# BSPD_Test_Board_manufactured_2016-12-12.net
KiCad netlist of a schematic drawn in EAGLE
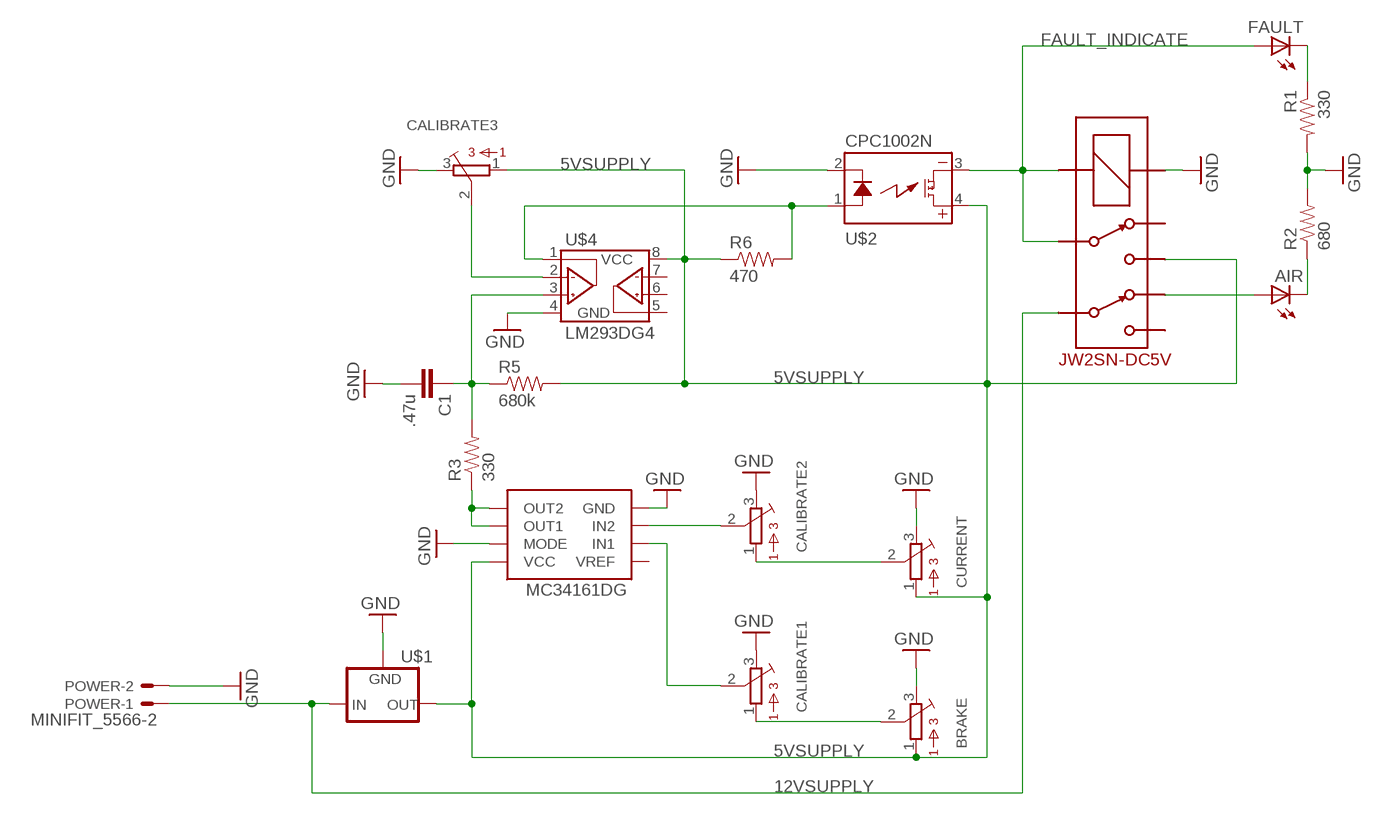
[diagram p0: schematic, sheet 1]

(export (version "E")
  (design (tool "Eeschema 10.0.6"))
  (components
    (comp (ref "AIR")
      (value "LED-5MM")
      (footprint "eagle-import:LED-5MM")
      (libsource (lib "eagle-import") (part "LED-5MM"))
    )
    (comp (ref "BRAKE")
      (value "TRIMPOT_3296C")
      (footprint "eagle-import:TRIMPOT_3296")
      (libsource (lib "eagle-import") (part "TRIMPOT_3296C"))
    )
    (comp (ref "C1")
      (value ".47u")
      (footprint "eagle-import:CAP-PTH-SMALLEZ")
      (libsource (lib "eagle-import") (part "CAPEZ"))
    )
    (comp (ref "CALIBRATE1")
      (value "TRIMPOT_3296C")
      (footprint "eagle-import:TRIMPOT_3296")
      (libsource (lib "eagle-import") (part "TRIMPOT_3296C"))
    )
    (comp (ref "CALIBRATE2")
      (value "TRIMPOT_3296C")
      (footprint "eagle-import:TRIMPOT_3296")
      (libsource (lib "eagle-import") (part "TRIMPOT_3296C"))
    )
    (comp (ref "CALIBRATE3")
      (value "TRIMPOT_3296C")
      (footprint "eagle-import:TRIMPOT_3296")
      (libsource (lib "eagle-import") (part "TRIMPOT_3296C"))
    )
    (comp (ref "CURRENT")
      (value "TRIMPOT_3296C")
      (footprint "eagle-import:TRIMPOT_3296")
      (libsource (lib "eagle-import") (part "TRIMPOT_3296C"))
    )
    (comp (ref "FAULT")
      (value "LED-5MM")
      (footprint "eagle-import:LED-5MM")
      (libsource (lib "eagle-import") (part "LED-5MM"))
    )
    (comp (ref "MC34161DG")
      (value "VOLTAGE_MONITOR_MC34161DG")
      (footprint "eagle-import:SOIC-08")
      (libsource (lib "eagle-import") (part "VOLTAGE_MONITOR_MC34161DG"))
    )
    (comp (ref "POWER")
      (value "MINIFIT_5566-2")
      (footprint "eagle-import:MINIFIT_5566-2")
      (libsource (lib "eagle-import") (part "MINIFIT_5566-2"))
    )
    (comp (ref "R1")
      (value "330")
      (footprint "eagle-import:0805")
      (libsource (lib "eagle-import") (part "RESISTOR0805-RES"))
    )
    (comp (ref "R2")
      (value "680")
      (footprint "eagle-import:0805")
      (libsource (lib "eagle-import") (part "RESISTOR0805-RES"))
    )
    (comp (ref "R3")
      (value "330")
      (footprint "eagle-import:0805")
      (libsource (lib "eagle-import") (part "RESISTOR0805-RES"))
    )
    (comp (ref "R5")
      (value "680k")
      (footprint "eagle-import:AXIAL-0.3EZ")
      (libsource (lib "eagle-import") (part "RESISTOREZ"))
    )
    (comp (ref "R6")
      (value "470")
      (footprint "eagle-import:0805")
      (libsource (lib "eagle-import") (part "RESISTOR0805-RES"))
    )
    (comp (ref "U$1")
      (value "5V_REGULATOR_LM340-NLM340MPX-5.0/NOPB")
      (footprint "eagle-import:SOT223")
      (libsource (lib "eagle-import") (part "5V_REGULATOR_LM340-NLM340MPX-5.0/NOPB"))
    )
    (comp (ref "U$2")
      (value "CPC1002N")
      (footprint "eagle-import:SOP04")
      (libsource (lib "eagle-import") (part "CPC1002N"))
    )
    (comp (ref "U$3")
      (value "DPDT_RELAY_PANASONIC_JW2SN-DC5V")
      (footprint "eagle-import:DPDT_RELAY_PANASONIC_JW2SN")
      (libsource (lib "eagle-import") (part "DPDT_RELAY_PANASONIC_JW2SN-DC5V"))
    )
    (comp (ref "U$4")
      (value "LM293DG4")
      (footprint "eagle-import:SOIC-08")
      (libsource (lib "eagle-import") (part "LM293DG4"))
    )
  )
  (nets
    (net (code "1") (name "/5VSUPPLY") (class "Default")
      (node (ref "BRAKE") (pin "1") (pinfunction "1_1") (pintype "passive"))
      (node (ref "CALIBRATE3") (pin "1") (pinfunction "1_1") (pintype "passive"))
      (node (ref "CURRENT") (pin "1") (pinfunction "1_1") (pintype "passive"))
      (node (ref "MC34161DG") (pin "8") (pinfunction "VCC_8") (pintype "passive"))
      (node (ref "R5") (pin "P$2") (pinfunction "2_P$2") (pintype "passive"))
      (node (ref "R6") (pin "1") (pinfunction "1_1") (pintype "passive"))
      (node (ref "U$1") (pin "3") (pinfunction "OUT_3") (pintype "output"))
      (node (ref "U$2") (pin "4") (pinfunction "DC+_4") (pintype "passive"))
      (node (ref "U$3") (pin "4") (pinfunction "4_4") (pintype "bidirectional"))
      (node (ref "U$4") (pin "8") (pinfunction "VCC_8") (pintype "passive"))
    )
    (net (code "2") (name "/12VSUPPLY") (class "Default")
      (node (ref "POWER") (pin "1") (pinfunction "S_1") (pintype "passive"))
      (node (ref "U$1") (pin "1") (pinfunction "IN_1") (pintype "input"))
      (node (ref "U$3") (pin "6") (pinfunction "6_6") (pintype "bidirectional"))
    )
    (net (code "3") (name "/FAULT_INDICATE") (class "Default")
      (node (ref "FAULT") (pin "A") (pinfunction "A_A") (pintype "passive"))
      (node (ref "U$2") (pin "3") (pinfunction "DC-_3") (pintype "passive"))
      (node (ref "U$3") (pin "3") (pinfunction "3_3") (pintype "bidirectional"))
      (node (ref "U$3") (pin "COIL-") (pinfunction "COIL-_COIL-") (pintype "bidirectional"))
    )
    (net (code "4") (name "GND") (class "Default")
      (node (ref "BRAKE") (pin "3") (pinfunction "3_3") (pintype "passive"))
      (node (ref "C1") (pin "2") (pinfunction "2_2") (pintype "passive"))
      (node (ref "CALIBRATE1") (pin "3") (pinfunction "3_3") (pintype "passive"))
      (node (ref "CALIBRATE2") (pin "3") (pinfunction "3_3") (pintype "passive"))
      (node (ref "CALIBRATE3") (pin "3") (pinfunction "3_3") (pintype "passive"))
      (node (ref "CURRENT") (pin "3") (pinfunction "3_3") (pintype "passive"))
      (node (ref "MC34161DG") (pin "4") (pinfunction "GND_4") (pintype "passive"))
      (node (ref "MC34161DG") (pin "7") (pinfunction "MODE_7") (pintype "passive"))
      (node (ref "POWER") (pin "2") (pinfunction "S_2") (pintype "passive"))
      (node (ref "R1") (pin "2") (pinfunction "2_2") (pintype "passive"))
      (node (ref "R2") (pin "2") (pinfunction "2_2") (pintype "passive"))
      (node (ref "U$1") (pin "2") (pinfunction "GND_2") (pintype "input"))
      (node (ref "U$1") (pin "4") (pinfunction "GND_4") (pintype "input"))
      (node (ref "U$2") (pin "2") (pinfunction "CONTROL-_2") (pintype "passive"))
      (node (ref "U$3") (pin "COIL+") (pinfunction "COIL+_COIL+") (pintype "bidirectional"))
      (node (ref "U$4") (pin "4") (pinfunction "GND_4") (pintype "passive"))
    )
    (net (code "5") (name "Net-(AIR-C)") (class "Default")
      (node (ref "AIR") (pin "K") (pinfunction "C_K") (pintype "passive"))
      (node (ref "R2") (pin "1") (pinfunction "1_1") (pintype "passive"))
    )
    (net (code "6") (name "Net-(AIR-PadA)") (class "Default")
      (node (ref "AIR") (pin "A") (pinfunction "A_A") (pintype "passive"))
      (node (ref "U$3") (pin "7") (pinfunction "7_7") (pintype "bidirectional"))
    )
    (net (code "7") (name "Net-(BRAKE-Pad2)") (class "Default")
      (node (ref "BRAKE") (pin "2") (pinfunction "2_2") (pintype "passive"))
      (node (ref "CALIBRATE1") (pin "1") (pinfunction "1_1") (pintype "passive"))
    )
    (net (code "8") (name "Net-(CALIBRATE2-Pad1)") (class "Default")
      (node (ref "CALIBRATE2") (pin "1") (pinfunction "1_1") (pintype "passive"))
      (node (ref "CURRENT") (pin "2") (pinfunction "2_2") (pintype "passive"))
    )
    (net (code "9") (name "Net-(FAULT-C)") (class "Default")
      (node (ref "FAULT") (pin "K") (pinfunction "C_K") (pintype "passive"))
      (node (ref "R1") (pin "1") (pinfunction "1_1") (pintype "passive"))
    )
    (net (code "10") (name "Net-(MC34161DG-IN1)") (class "Default")
      (node (ref "CALIBRATE1") (pin "2") (pinfunction "2_2") (pintype "passive"))
      (node (ref "MC34161DG") (pin "2") (pinfunction "IN1_2") (pintype "passive"))
    )
    (net (code "11") (name "Net-(MC34161DG-IN2)") (class "Default")
      (node (ref "CALIBRATE2") (pin "2") (pinfunction "2_2") (pintype "passive"))
      (node (ref "MC34161DG") (pin "3") (pinfunction "IN2_3") (pintype "passive"))
    )
    (net (code "12") (name "Net-(MC34161DG-OUT1)") (class "Default")
      (node (ref "MC34161DG") (pin "5") (pinfunction "OUT2_5") (pintype "passive"))
      (node (ref "MC34161DG") (pin "6") (pinfunction "OUT1_6") (pintype "passive"))
      (node (ref "R3") (pin "1") (pinfunction "1_1") (pintype "passive"))
    )
    (net (code "13") (name "Net-(R5-1)") (class "Default")
      (node (ref "C1") (pin "1") (pinfunction "1_1") (pintype "passive"))
      (node (ref "R3") (pin "2") (pinfunction "2_2") (pintype "passive"))
      (node (ref "R5") (pin "P$1") (pinfunction "1_P$1") (pintype "passive"))
      (node (ref "U$4") (pin "3") (pinfunction "1IN+_3") (pintype "passive"))
    )
    (net (code "14") (name "Net-(U$2-CONTROL+)") (class "Default")
      (node (ref "R6") (pin "2") (pinfunction "2_2") (pintype "passive"))
      (node (ref "U$2") (pin "1") (pinfunction "CONTROL+_1") (pintype "passive"))
      (node (ref "U$4") (pin "1") (pinfunction "1OUT_1") (pintype "passive"))
    )
    (net (code "15") (name "Net-(U$4-1IN-)") (class "Default")
      (node (ref "CALIBRATE3") (pin "2") (pinfunction "2_2") (pintype "passive"))
      (node (ref "U$4") (pin "2") (pinfunction "1IN-_2") (pintype "passive"))
    )
    (net (code "16") (name "unconnected-(MC34161DG-VREF-Pad1)") (class "Default")
      (node (ref "MC34161DG") (pin "1") (pinfunction "VREF_1") (pintype "passive"))
    )
    (net (code "17") (name "unconnected-(U$3-Pad2)") (class "Default")
      (node (ref "U$3") (pin "2") (pinfunction "2_2") (pintype "bidirectional"))
    )
    (net (code "18") (name "unconnected-(U$3-Pad5)") (class "Default")
      (node (ref "U$3") (pin "5") (pinfunction "5_5") (pintype "bidirectional"))
    )
    (net (code "19") (name "unconnected-(U$4-2IN+-Pad5)") (class "Default")
      (node (ref "U$4") (pin "5") (pinfunction "2IN+_5") (pintype "passive"))
    )
    (net (code "20") (name "unconnected-(U$4-2IN--Pad6)") (class "Default")
      (node (ref "U$4") (pin "6") (pinfunction "2IN-_6") (pintype "passive"))
    )
    (net (code "21") (name "unconnected-(U$4-2OUT-Pad7)") (class "Default")
      (node (ref "U$4") (pin "7") (pinfunction "2OUT_7") (pintype "passive"))
    )
  )
)
